# 330E_Transistor_Logic.net
KiCad netlist of a schematic drawn in Altium Designer
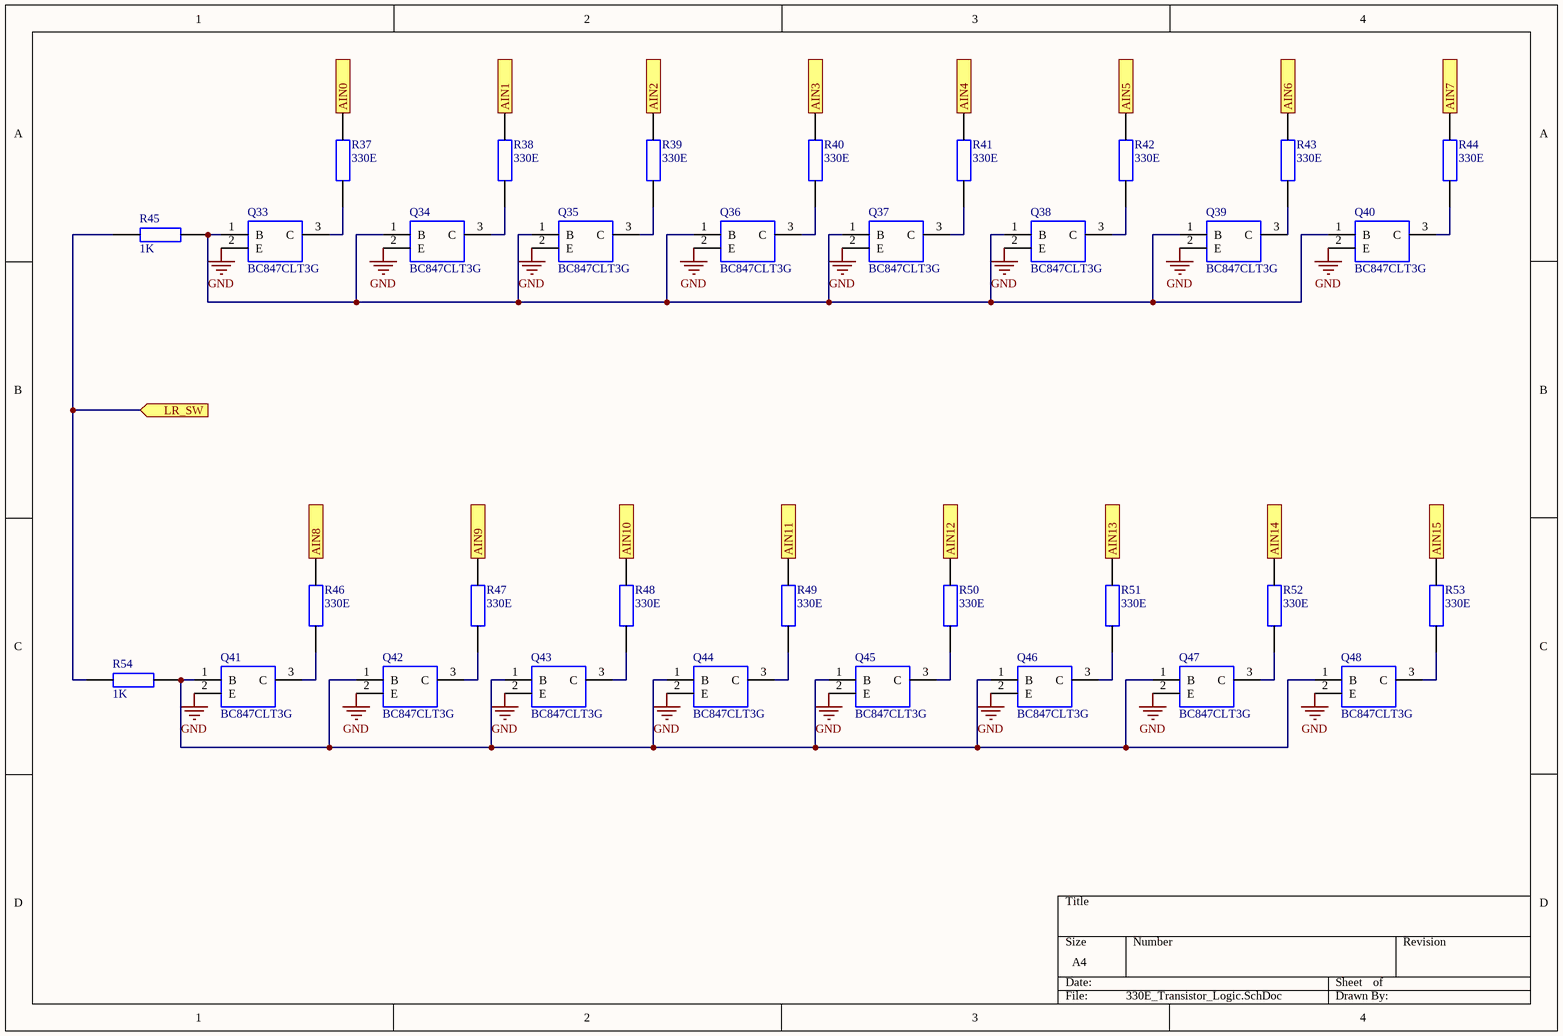
[diagram p0: 330E_Transistor_Logic.SchDoc]

(export (version "E")
  (design (tool "Eeschema 10.0.6"))
  (components
    (comp (ref "Q33")
      (value "BC847CLT3G")
      (footprint "SOT96P237X111-3N")
      (fields (field (name "MOUSER PART NUMBER") "863-BC847CLT3G"))
      (libsource (lib "BC847CLT3G") (part "BC847CLT3G"))
    )
    (comp (ref "Q34")
      (value "BC847CLT3G")
      (footprint "SOT96P237X111-3N")
      (fields (field (name "MOUSER PART NUMBER") "863-BC847CLT3G"))
      (libsource (lib "BC847CLT3G") (part "BC847CLT3G"))
    )
    (comp (ref "Q35")
      (value "BC847CLT3G")
      (footprint "SOT96P237X111-3N")
      (fields (field (name "MOUSER PART NUMBER") "863-BC847CLT3G"))
      (libsource (lib "BC847CLT3G") (part "BC847CLT3G"))
    )
    (comp (ref "Q36")
      (value "BC847CLT3G")
      (footprint "SOT96P237X111-3N")
      (fields (field (name "MOUSER PART NUMBER") "863-BC847CLT3G"))
      (libsource (lib "BC847CLT3G") (part "BC847CLT3G"))
    )
    (comp (ref "Q37")
      (value "BC847CLT3G")
      (footprint "SOT96P237X111-3N")
      (fields (field (name "MOUSER PART NUMBER") "863-BC847CLT3G"))
      (libsource (lib "BC847CLT3G") (part "BC847CLT3G"))
    )
    (comp (ref "Q38")
      (value "BC847CLT3G")
      (footprint "SOT96P237X111-3N")
      (fields (field (name "MOUSER PART NUMBER") "863-BC847CLT3G"))
      (libsource (lib "BC847CLT3G") (part "BC847CLT3G"))
    )
    (comp (ref "Q39")
      (value "BC847CLT3G")
      (footprint "SOT96P237X111-3N")
      (fields (field (name "MOUSER PART NUMBER") "863-BC847CLT3G"))
      (libsource (lib "BC847CLT3G") (part "BC847CLT3G"))
    )
    (comp (ref "Q40")
      (value "BC847CLT3G")
      (footprint "SOT96P237X111-3N")
      (fields (field (name "MOUSER PART NUMBER") "863-BC847CLT3G"))
      (libsource (lib "BC847CLT3G") (part "BC847CLT3G"))
    )
    (comp (ref "Q41")
      (value "BC847CLT3G")
      (footprint "SOT96P237X111-3N")
      (fields (field (name "MOUSER PART NUMBER") "863-BC847CLT3G"))
      (libsource (lib "BC847CLT3G") (part "BC847CLT3G"))
    )
    (comp (ref "Q42")
      (value "BC847CLT3G")
      (footprint "SOT96P237X111-3N")
      (fields (field (name "MOUSER PART NUMBER") "863-BC847CLT3G"))
      (libsource (lib "BC847CLT3G") (part "BC847CLT3G"))
    )
    (comp (ref "Q43")
      (value "BC847CLT3G")
      (footprint "SOT96P237X111-3N")
      (fields (field (name "MOUSER PART NUMBER") "863-BC847CLT3G"))
      (libsource (lib "BC847CLT3G") (part "BC847CLT3G"))
    )
    (comp (ref "Q44")
      (value "BC847CLT3G")
      (footprint "SOT96P237X111-3N")
      (fields (field (name "MOUSER PART NUMBER") "863-BC847CLT3G"))
      (libsource (lib "BC847CLT3G") (part "BC847CLT3G"))
    )
    (comp (ref "Q45")
      (value "BC847CLT3G")
      (footprint "SOT96P237X111-3N")
      (fields (field (name "MOUSER PART NUMBER") "863-BC847CLT3G"))
      (libsource (lib "BC847CLT3G") (part "BC847CLT3G"))
    )
    (comp (ref "Q46")
      (value "BC847CLT3G")
      (footprint "SOT96P237X111-3N")
      (fields (field (name "MOUSER PART NUMBER") "863-BC847CLT3G"))
      (libsource (lib "BC847CLT3G") (part "BC847CLT3G"))
    )
    (comp (ref "Q47")
      (value "BC847CLT3G")
      (footprint "SOT96P237X111-3N")
      (fields (field (name "MOUSER PART NUMBER") "863-BC847CLT3G"))
      (libsource (lib "BC847CLT3G") (part "BC847CLT3G"))
    )
    (comp (ref "Q48")
      (value "BC847CLT3G")
      (footprint "SOT96P237X111-3N")
      (fields (field (name "MOUSER PART NUMBER") "863-BC847CLT3G"))
      (libsource (lib "BC847CLT3G") (part "BC847CLT3G"))
    )
    (comp (ref "R37")
      (value "330E")
      (footprint "RESC1608X55N")
      (description "YAGEO (PHYCOMP) - RC0603FR-07330RL - RES, THICK FILM, 330R, 1%, 0.1W, 0603")
      (fields
        (field (name "MANUFACTURER_PART_NUMBER") "RC0603FR-07330RL")
        (field (name "MOUSER PART NUMBER") "603-RC0603FR-07330RL")
      )
      (libsource (lib "330E_0603") (part "RC0603FR-07330RL"))
    )
    (comp (ref "R38")
      (value "330E")
      (footprint "RESC1608X55N")
      (description "YAGEO (PHYCOMP) - RC0603FR-07330RL - RES, THICK FILM, 330R, 1%, 0.1W, 0603")
      (fields
        (field (name "MANUFACTURER_PART_NUMBER") "RC0603FR-07330RL")
        (field (name "MOUSER PART NUMBER") "603-RC0603FR-07330RL")
      )
      (libsource (lib "330E_0603") (part "RC0603FR-07330RL"))
    )
    (comp (ref "R39")
      (value "330E")
      (footprint "RESC1608X55N")
      (description "YAGEO (PHYCOMP) - RC0603FR-07330RL - RES, THICK FILM, 330R, 1%, 0.1W, 0603")
      (fields
        (field (name "MANUFACTURER_PART_NUMBER") "RC0603FR-07330RL")
        (field (name "MOUSER PART NUMBER") "603-RC0603FR-07330RL")
      )
      (libsource (lib "330E_0603") (part "RC0603FR-07330RL"))
    )
    (comp (ref "R40")
      (value "330E")
      (footprint "RESC1608X55N")
      (description "YAGEO (PHYCOMP) - RC0603FR-07330RL - RES, THICK FILM, 330R, 1%, 0.1W, 0603")
      (fields
        (field (name "MANUFACTURER_PART_NUMBER") "RC0603FR-07330RL")
        (field (name "MOUSER PART NUMBER") "603-RC0603FR-07330RL")
      )
      (libsource (lib "330E_0603") (part "RC0603FR-07330RL"))
    )
    (comp (ref "R41")
      (value "330E")
      (footprint "RESC1608X55N")
      (description "YAGEO (PHYCOMP) - RC0603FR-07330RL - RES, THICK FILM, 330R, 1%, 0.1W, 0603")
      (fields
        (field (name "MANUFACTURER_PART_NUMBER") "RC0603FR-07330RL")
        (field (name "MOUSER PART NUMBER") "603-RC0603FR-07330RL")
      )
      (libsource (lib "330E_0603") (part "RC0603FR-07330RL"))
    )
    (comp (ref "R42")
      (value "330E")
      (footprint "RESC1608X55N")
      (description "YAGEO (PHYCOMP) - RC0603FR-07330RL - RES, THICK FILM, 330R, 1%, 0.1W, 0603")
      (fields
        (field (name "MANUFACTURER_PART_NUMBER") "RC0603FR-07330RL")
        (field (name "MOUSER PART NUMBER") "603-RC0603FR-07330RL")
      )
      (libsource (lib "330E_0603") (part "RC0603FR-07330RL"))
    )
    (comp (ref "R43")
      (value "330E")
      (footprint "RESC1608X55N")
      (description "YAGEO (PHYCOMP) - RC0603FR-07330RL - RES, THICK FILM, 330R, 1%, 0.1W, 0603")
      (fields
        (field (name "MANUFACTURER_PART_NUMBER") "RC0603FR-07330RL")
        (field (name "MOUSER PART NUMBER") "603-RC0603FR-07330RL")
      )
      (libsource (lib "330E_0603") (part "RC0603FR-07330RL"))
    )
    (comp (ref "R44")
      (value "330E")
      (footprint "RESC1608X55N")
      (description "YAGEO (PHYCOMP) - RC0603FR-07330RL - RES, THICK FILM, 330R, 1%, 0.1W, 0603")
      (fields
        (field (name "MANUFACTURER_PART_NUMBER") "RC0603FR-07330RL")
        (field (name "MOUSER PART NUMBER") "603-RC0603FR-07330RL")
      )
      (libsource (lib "330E_0603") (part "RC0603FR-07330RL"))
    )
    (comp (ref "R45")
      (value "1K")
      (footprint "RESC1608X55N")
      (description "YAGEO (PHYCOMP) - RC0603JR-071KL - RES, THICK FILM, 1K, 5%, 0.1W, 0603")
      (fields
        (field (name "MANUFACTURER_PART_NUMBER") "RC0603JR-071KL")
        (field (name "MOUSER PART NUMBER") "603-RC0603JR-071KL")
      )
      (libsource (lib "1K_0603") (part "RC0603JR-071KL"))
    )
    (comp (ref "R46")
      (value "330E")
      (footprint "RESC1608X55N")
      (description "YAGEO (PHYCOMP) - RC0603FR-07330RL - RES, THICK FILM, 330R, 1%, 0.1W, 0603")
      (fields
        (field (name "MANUFACTURER_PART_NUMBER") "RC0603FR-07330RL")
        (field (name "MOUSER PART NUMBER") "603-RC0603FR-07330RL")
      )
      (libsource (lib "330E_0603") (part "RC0603FR-07330RL"))
    )
    (comp (ref "R47")
      (value "330E")
      (footprint "RESC1608X55N")
      (description "YAGEO (PHYCOMP) - RC0603FR-07330RL - RES, THICK FILM, 330R, 1%, 0.1W, 0603")
      (fields
        (field (name "MANUFACTURER_PART_NUMBER") "RC0603FR-07330RL")
        (field (name "MOUSER PART NUMBER") "603-RC0603FR-07330RL")
      )
      (libsource (lib "330E_0603") (part "RC0603FR-07330RL"))
    )
    (comp (ref "R48")
      (value "330E")
      (footprint "RESC1608X55N")
      (description "YAGEO (PHYCOMP) - RC0603FR-07330RL - RES, THICK FILM, 330R, 1%, 0.1W, 0603")
      (fields
        (field (name "MANUFACTURER_PART_NUMBER") "RC0603FR-07330RL")
        (field (name "MOUSER PART NUMBER") "603-RC0603FR-07330RL")
      )
      (libsource (lib "330E_0603") (part "RC0603FR-07330RL"))
    )
    (comp (ref "R49")
      (value "330E")
      (footprint "RESC1608X55N")
      (description "YAGEO (PHYCOMP) - RC0603FR-07330RL - RES, THICK FILM, 330R, 1%, 0.1W, 0603")
      (fields
        (field (name "MANUFACTURER_PART_NUMBER") "RC0603FR-07330RL")
        (field (name "MOUSER PART NUMBER") "603-RC0603FR-07330RL")
      )
      (libsource (lib "330E_0603") (part "RC0603FR-07330RL"))
    )
    (comp (ref "R50")
      (value "330E")
      (footprint "RESC1608X55N")
      (description "YAGEO (PHYCOMP) - RC0603FR-07330RL - RES, THICK FILM, 330R, 1%, 0.1W, 0603")
      (fields
        (field (name "MANUFACTURER_PART_NUMBER") "RC0603FR-07330RL")
        (field (name "MOUSER PART NUMBER") "603-RC0603FR-07330RL")
      )
      (libsource (lib "330E_0603") (part "RC0603FR-07330RL"))
    )
    (comp (ref "R51")
      (value "330E")
      (footprint "RESC1608X55N")
      (description "YAGEO (PHYCOMP) - RC0603FR-07330RL - RES, THICK FILM, 330R, 1%, 0.1W, 0603")
      (fields
        (field (name "MANUFACTURER_PART_NUMBER") "RC0603FR-07330RL")
        (field (name "MOUSER PART NUMBER") "603-RC0603FR-07330RL")
      )
      (libsource (lib "330E_0603") (part "RC0603FR-07330RL"))
    )
    (comp (ref "R52")
      (value "330E")
      (footprint "RESC1608X55N")
      (description "YAGEO (PHYCOMP) - RC0603FR-07330RL - RES, THICK FILM, 330R, 1%, 0.1W, 0603")
      (fields
        (field (name "MANUFACTURER_PART_NUMBER") "RC0603FR-07330RL")
        (field (name "MOUSER PART NUMBER") "603-RC0603FR-07330RL")
      )
      (libsource (lib "330E_0603") (part "RC0603FR-07330RL"))
    )
    (comp (ref "R53")
      (value "330E")
      (footprint "RESC1608X55N")
      (description "YAGEO (PHYCOMP) - RC0603FR-07330RL - RES, THICK FILM, 330R, 1%, 0.1W, 0603")
      (fields
        (field (name "MANUFACTURER_PART_NUMBER") "RC0603FR-07330RL")
        (field (name "MOUSER PART NUMBER") "603-RC0603FR-07330RL")
      )
      (libsource (lib "330E_0603") (part "RC0603FR-07330RL"))
    )
    (comp (ref "R54")
      (value "1K")
      (footprint "RESC1608X55N")
      (description "YAGEO (PHYCOMP) - RC0603JR-071KL - RES, THICK FILM, 1K, 5%, 0.1W, 0603")
      (fields
        (field (name "MANUFACTURER_PART_NUMBER") "RC0603JR-071KL")
        (field (name "MOUSER PART NUMBER") "603-RC0603JR-071KL")
      )
      (libsource (lib "1K_0603") (part "RC0603JR-071KL"))
    )
  )
  (nets
    (net (code "1") (name "/AIN0") (class "Default")
      (node (ref "R37") (pin "2") (pinfunction "2_2") (pintype "passive"))
    )
    (net (code "2") (name "/AIN1") (class "Default")
      (node (ref "R38") (pin "2") (pinfunction "2_2") (pintype "passive"))
    )
    (net (code "3") (name "/AIN2") (class "Default")
      (node (ref "R39") (pin "2") (pinfunction "2_2") (pintype "passive"))
    )
    (net (code "4") (name "/AIN3") (class "Default")
      (node (ref "R40") (pin "2") (pinfunction "2_2") (pintype "passive"))
    )
    (net (code "5") (name "/AIN4") (class "Default")
      (node (ref "R41") (pin "2") (pinfunction "2_2") (pintype "passive"))
    )
    (net (code "6") (name "/AIN5") (class "Default")
      (node (ref "R42") (pin "2") (pinfunction "2_2") (pintype "passive"))
    )
    (net (code "7") (name "/AIN6") (class "Default")
      (node (ref "R43") (pin "2") (pinfunction "2_2") (pintype "passive"))
    )
    (net (code "8") (name "/AIN7") (class "Default")
      (node (ref "R44") (pin "2") (pinfunction "2_2") (pintype "passive"))
    )
    (net (code "9") (name "/AIN8") (class "Default")
      (node (ref "R46") (pin "2") (pinfunction "2_2") (pintype "passive"))
    )
    (net (code "10") (name "/AIN9") (class "Default")
      (node (ref "R47") (pin "2") (pinfunction "2_2") (pintype "passive"))
    )
    (net (code "11") (name "/AIN10") (class "Default")
      (node (ref "R48") (pin "2") (pinfunction "2_2") (pintype "passive"))
    )
    (net (code "12") (name "/AIN11") (class "Default")
      (node (ref "R49") (pin "2") (pinfunction "2_2") (pintype "passive"))
    )
    (net (code "13") (name "/AIN12") (class "Default")
      (node (ref "R50") (pin "2") (pinfunction "2_2") (pintype "passive"))
    )
    (net (code "14") (name "/AIN13") (class "Default")
      (node (ref "R51") (pin "2") (pinfunction "2_2") (pintype "passive"))
    )
    (net (code "15") (name "/AIN14") (class "Default")
      (node (ref "R52") (pin "2") (pinfunction "2_2") (pintype "passive"))
    )
    (net (code "16") (name "/AIN15") (class "Default")
      (node (ref "R53") (pin "2") (pinfunction "2_2") (pintype "passive"))
    )
    (net (code "17") (name "/LR_SW") (class "Default")
      (node (ref "R45") (pin "1") (pinfunction "1_1") (pintype "passive"))
      (node (ref "R54") (pin "1") (pinfunction "1_1") (pintype "passive"))
    )
    (net (code "18") (name "GND") (class "Default")
      (node (ref "Q33") (pin "2") (pinfunction "E_2") (pintype "passive"))
      (node (ref "Q34") (pin "2") (pinfunction "E_2") (pintype "passive"))
      (node (ref "Q35") (pin "2") (pinfunction "E_2") (pintype "passive"))
      (node (ref "Q36") (pin "2") (pinfunction "E_2") (pintype "passive"))
      (node (ref "Q37") (pin "2") (pinfunction "E_2") (pintype "passive"))
      (node (ref "Q38") (pin "2") (pinfunction "E_2") (pintype "passive"))
      (node (ref "Q39") (pin "2") (pinfunction "E_2") (pintype "passive"))
      (node (ref "Q40") (pin "2") (pinfunction "E_2") (pintype "passive"))
      (node (ref "Q41") (pin "2") (pinfunction "E_2") (pintype "passive"))
      (node (ref "Q42") (pin "2") (pinfunction "E_2") (pintype "passive"))
      (node (ref "Q43") (pin "2") (pinfunction "E_2") (pintype "passive"))
      (node (ref "Q44") (pin "2") (pinfunction "E_2") (pintype "passive"))
      (node (ref "Q45") (pin "2") (pinfunction "E_2") (pintype "passive"))
      (node (ref "Q46") (pin "2") (pinfunction "E_2") (pintype "passive"))
      (node (ref "Q47") (pin "2") (pinfunction "E_2") (pintype "passive"))
      (node (ref "Q48") (pin "2") (pinfunction "E_2") (pintype "passive"))
    )
    (net (code "19") (name "Net-(Q33-B)") (class "Default")
      (node (ref "Q33") (pin "1") (pinfunction "B_1") (pintype "passive"))
      (node (ref "Q34") (pin "1") (pinfunction "B_1") (pintype "passive"))
      (node (ref "Q35") (pin "1") (pinfunction "B_1") (pintype "passive"))
      (node (ref "Q36") (pin "1") (pinfunction "B_1") (pintype "passive"))
      (node (ref "Q37") (pin "1") (pinfunction "B_1") (pintype "passive"))
      (node (ref "Q38") (pin "1") (pinfunction "B_1") (pintype "passive"))
      (node (ref "Q39") (pin "1") (pinfunction "B_1") (pintype "passive"))
      (node (ref "Q40") (pin "1") (pinfunction "B_1") (pintype "passive"))
      (node (ref "R45") (pin "2") (pinfunction "2_2") (pintype "passive"))
    )
    (net (code "20") (name "Net-(Q33-C)") (class "Default")
      (node (ref "Q33") (pin "3") (pinfunction "C_3") (pintype "passive"))
      (node (ref "R37") (pin "1") (pinfunction "1_1") (pintype "passive"))
    )
    (net (code "21") (name "Net-(Q34-C)") (class "Default")
      (node (ref "Q34") (pin "3") (pinfunction "C_3") (pintype "passive"))
      (node (ref "R38") (pin "1") (pinfunction "1_1") (pintype "passive"))
    )
    (net (code "22") (name "Net-(Q35-C)") (class "Default")
      (node (ref "Q35") (pin "3") (pinfunction "C_3") (pintype "passive"))
      (node (ref "R39") (pin "1") (pinfunction "1_1") (pintype "passive"))
    )
    (net (code "23") (name "Net-(Q36-C)") (class "Default")
      (node (ref "Q36") (pin "3") (pinfunction "C_3") (pintype "passive"))
      (node (ref "R40") (pin "1") (pinfunction "1_1") (pintype "passive"))
    )
    (net (code "24") (name "Net-(Q37-C)") (class "Default")
      (node (ref "Q37") (pin "3") (pinfunction "C_3") (pintype "passive"))
      (node (ref "R41") (pin "1") (pinfunction "1_1") (pintype "passive"))
    )
    (net (code "25") (name "Net-(Q38-C)") (class "Default")
      (node (ref "Q38") (pin "3") (pinfunction "C_3") (pintype "passive"))
      (node (ref "R42") (pin "1") (pinfunction "1_1") (pintype "passive"))
    )
    (net (code "26") (name "Net-(Q39-C)") (class "Default")
      (node (ref "Q39") (pin "3") (pinfunction "C_3") (pintype "passive"))
      (node (ref "R43") (pin "1") (pinfunction "1_1") (pintype "passive"))
    )
    (net (code "27") (name "Net-(Q40-C)") (class "Default")
      (node (ref "Q40") (pin "3") (pinfunction "C_3") (pintype "passive"))
      (node (ref "R44") (pin "1") (pinfunction "1_1") (pintype "passive"))
    )
    (net (code "28") (name "Net-(Q41-B)") (class "Default")
      (node (ref "Q41") (pin "1") (pinfunction "B_1") (pintype "passive"))
      (node (ref "Q42") (pin "1") (pinfunction "B_1") (pintype "passive"))
      (node (ref "Q43") (pin "1") (pinfunction "B_1") (pintype "passive"))
      (node (ref "Q44") (pin "1") (pinfunction "B_1") (pintype "passive"))
      (node (ref "Q45") (pin "1") (pinfunction "B_1") (pintype "passive"))
      (node (ref "Q46") (pin "1") (pinfunction "B_1") (pintype "passive"))
      (node (ref "Q47") (pin "1") (pinfunction "B_1") (pintype "passive"))
      (node (ref "Q48") (pin "1") (pinfunction "B_1") (pintype "passive"))
      (node (ref "R54") (pin "2") (pinfunction "2_2") (pintype "passive"))
    )
    (net (code "29") (name "Net-(Q41-C)") (class "Default")
      (node (ref "Q41") (pin "3") (pinfunction "C_3") (pintype "passive"))
      (node (ref "R46") (pin "1") (pinfunction "1_1") (pintype "passive"))
    )
    (net (code "30") (name "Net-(Q42-C)") (class "Default")
      (node (ref "Q42") (pin "3") (pinfunction "C_3") (pintype "passive"))
      (node (ref "R47") (pin "1") (pinfunction "1_1") (pintype "passive"))
    )
    (net (code "31") (name "Net-(Q43-C)") (class "Default")
      (node (ref "Q43") (pin "3") (pinfunction "C_3") (pintype "passive"))
      (node (ref "R48") (pin "1") (pinfunction "1_1") (pintype "passive"))
    )
    (net (code "32") (name "Net-(Q44-C)") (class "Default")
      (node (ref "Q44") (pin "3") (pinfunction "C_3") (pintype "passive"))
      (node (ref "R49") (pin "1") (pinfunction "1_1") (pintype "passive"))
    )
    (net (code "33") (name "Net-(Q45-C)") (class "Default")
      (node (ref "Q45") (pin "3") (pinfunction "C_3") (pintype "passive"))
      (node (ref "R50") (pin "1") (pinfunction "1_1") (pintype "passive"))
    )
    (net (code "34") (name "Net-(Q46-C)") (class "Default")
      (node (ref "Q46") (pin "3") (pinfunction "C_3") (pintype "passive"))
      (node (ref "R51") (pin "1") (pinfunction "1_1") (pintype "passive"))
    )
    (net (code "35") (name "Net-(Q47-C)") (class "Default")
      (node (ref "Q47") (pin "3") (pinfunction "C_3") (pintype "passive"))
      (node (ref "R52") (pin "1") (pinfunction "1_1") (pintype "passive"))
    )
    (net (code "36") (name "Net-(Q48-C)") (class "Default")
      (node (ref "Q48") (pin "3") (pinfunction "C_3") (pintype "passive"))
      (node (ref "R53") (pin "1") (pinfunction "1_1") (pintype "passive"))
    )
  )
)
